# pwm-generator.net
KiCad netlist of a schematic drawn in EAGLE
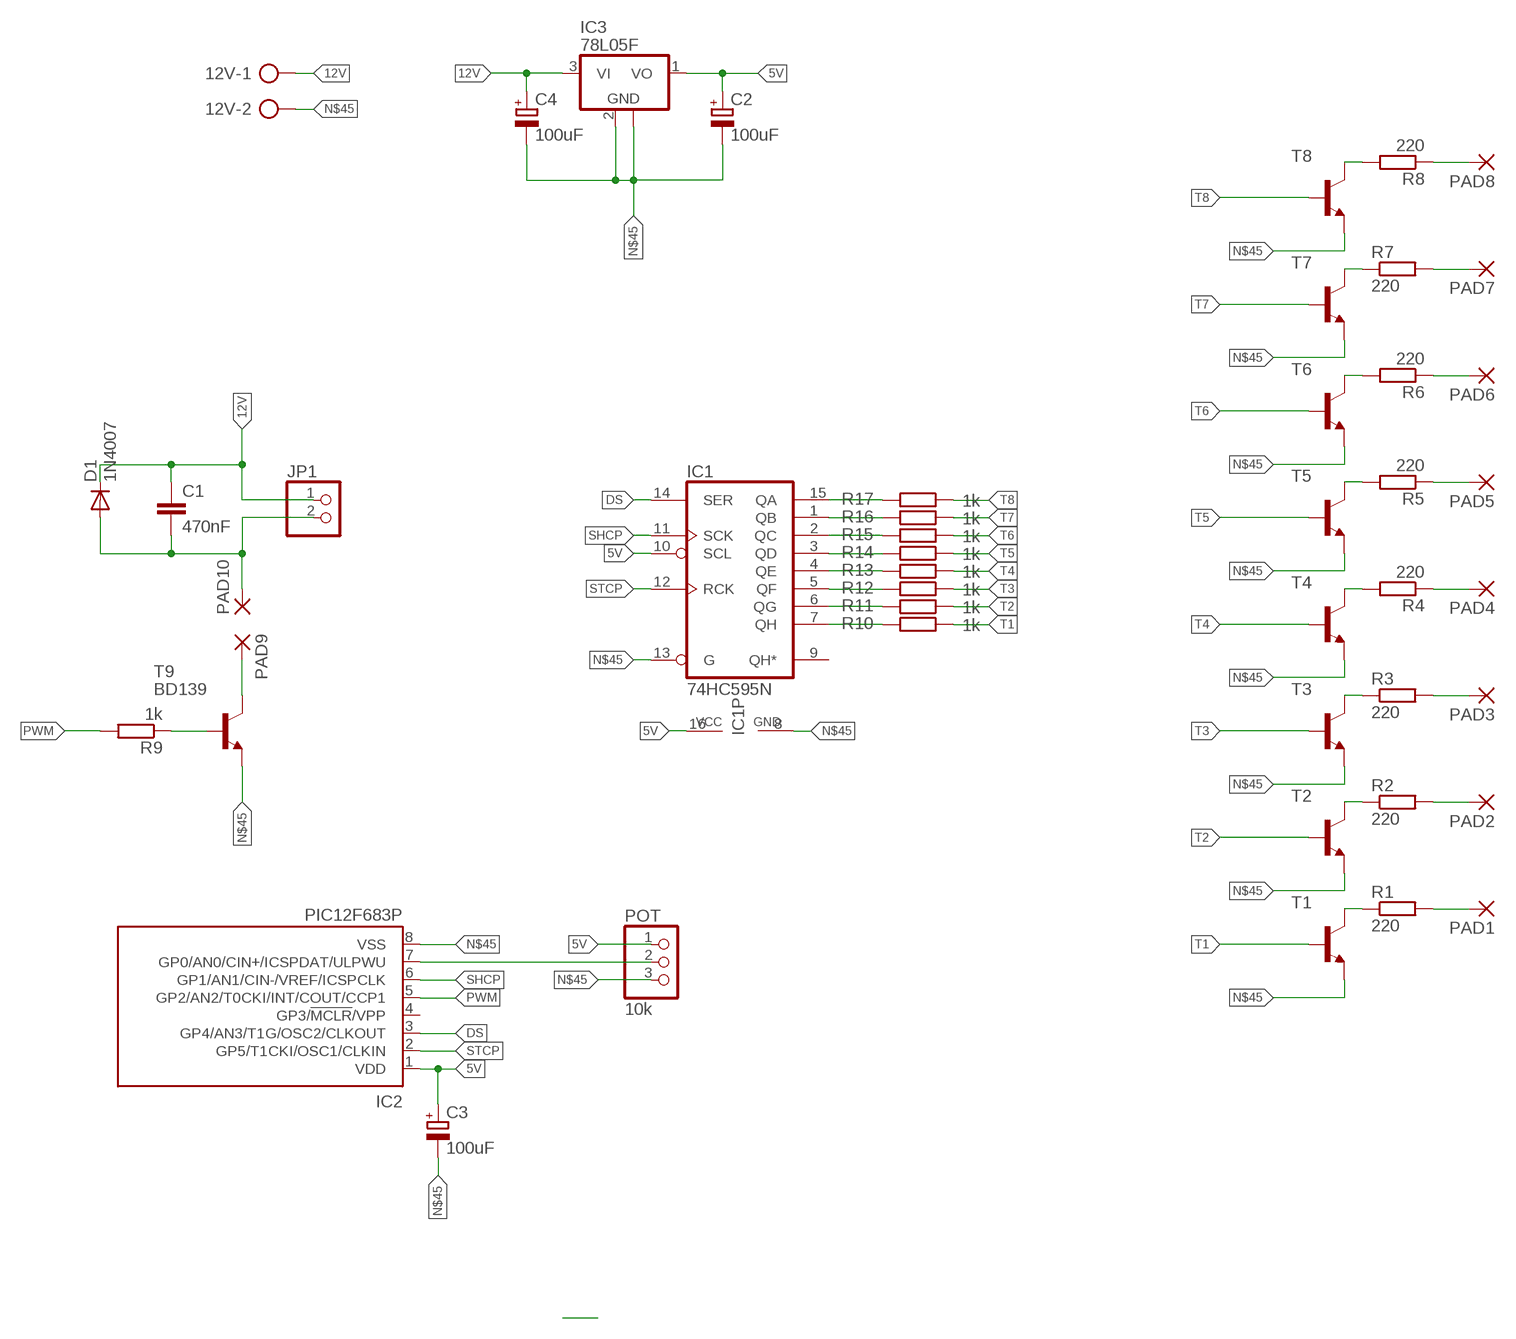
[diagram p0: schematic, sheet 1]

(export (version "E")
  (design (tool "Eeschema 10.0.6"))
  (components
    (comp (ref "12V")
      (value "AK500/2")
      (footprint "eagle-import:AK500_2")
      (libsource (lib "eagle-import") (part "AK500/2"))
    )
    (comp (ref "C1")
      (value "470nF")
      (footprint "eagle-import:C025-025X050")
      (libsource (lib "eagle-import") (part "C-EU025-025X050"))
    )
    (comp (ref "C2")
      (value "100uF")
      (footprint "eagle-import:E2-5")
      (libsource (lib "eagle-import") (part "CPOL-EUE2-5"))
    )
    (comp (ref "C3")
      (value "100uF")
      (footprint "eagle-import:E5-4")
      (libsource (lib "eagle-import") (part "CPOL-EUE5-4"))
    )
    (comp (ref "C4")
      (value "100uF")
      (footprint "eagle-import:E2-5")
      (libsource (lib "eagle-import") (part "CPOL-EUE2-5"))
    )
    (comp (ref "D1")
      (value "1N4007")
      (footprint "eagle-import:DO35-7")
      (libsource (lib "eagle-import") (part "1N4148DO35-7"))
    )
    (comp (ref "IC1")
      (value "74HC595N")
      (footprint "eagle-import:DIL16")
      (libsource (lib "eagle-import") (part "74595NHC"))
    )
    (comp (ref "IC2")
      (value "PIC12F683P")
      (footprint "eagle-import:DIL8")
      (fields (field (name "MF") "MICROCHIP") (field (name "MPN") "PIC12F683-I/P"))
      (libsource (lib "eagle-import") (part "PIC12F683P"))
    )
    (comp (ref "IC3")
      (value "78L05F")
      (footprint "eagle-import:SOT89")
      (libsource (lib "eagle-import") (part "78LF05"))
    )
    (comp (ref "JP1")
      (value "PINHD-1X2")
      (footprint "eagle-import:1X02")
      (libsource (lib "eagle-import") (part "PINHD-1X2"))
    )
    (comp (ref "PAD1")
      (value "SMD2")
      (footprint "eagle-import:SMD1,27-2,54")
      (libsource (lib "eagle-import") (part "SMD2"))
    )
    (comp (ref "PAD2")
      (value "SMD2")
      (footprint "eagle-import:SMD1,27-2,54")
      (libsource (lib "eagle-import") (part "SMD2"))
    )
    (comp (ref "PAD3")
      (value "SMD2")
      (footprint "eagle-import:SMD1,27-2,54")
      (libsource (lib "eagle-import") (part "SMD2"))
    )
    (comp (ref "PAD4")
      (value "SMD2")
      (footprint "eagle-import:SMD1,27-2,54")
      (libsource (lib "eagle-import") (part "SMD2"))
    )
    (comp (ref "PAD5")
      (value "SMD2")
      (footprint "eagle-import:SMD1,27-2,54")
      (libsource (lib "eagle-import") (part "SMD2"))
    )
    (comp (ref "PAD6")
      (value "SMD2")
      (footprint "eagle-import:SMD1,27-2,54")
      (libsource (lib "eagle-import") (part "SMD2"))
    )
    (comp (ref "PAD7")
      (value "SMD2")
      (footprint "eagle-import:SMD1,27-2,54")
      (libsource (lib "eagle-import") (part "SMD2"))
    )
    (comp (ref "PAD8")
      (value "SMD2")
      (footprint "eagle-import:SMD1,27-2,54")
      (libsource (lib "eagle-import") (part "SMD2"))
    )
    (comp (ref "PAD9")
      (value "1,6/0,8")
      (footprint "eagle-import:1,6_0,8")
      (libsource (lib "eagle-import") (part "1,6/0,8"))
    )
    (comp (ref "PAD10")
      (value "1,6/0,8")
      (footprint "eagle-import:1,6_0,8")
      (libsource (lib "eagle-import") (part "1,6/0,8"))
    )
    (comp (ref "POT")
      (value "10k")
      (footprint "eagle-import:1X03")
      (libsource (lib "eagle-import") (part "PINHD-1X3"))
    )
    (comp (ref "R1")
      (value "220")
      (footprint "eagle-import:M0805")
      (libsource (lib "eagle-import") (part "R-EU_M0805"))
    )
    (comp (ref "R2")
      (value "220")
      (footprint "eagle-import:M0805")
      (libsource (lib "eagle-import") (part "R-EU_M0805"))
    )
    (comp (ref "R3")
      (value "220")
      (footprint "eagle-import:M0805")
      (libsource (lib "eagle-import") (part "R-EU_M0805"))
    )
    (comp (ref "R4")
      (value "220")
      (footprint "eagle-import:M0805")
      (libsource (lib "eagle-import") (part "R-EU_M0805"))
    )
    (comp (ref "R5")
      (value "220")
      (footprint "eagle-import:M0805")
      (libsource (lib "eagle-import") (part "R-EU_M0805"))
    )
    (comp (ref "R6")
      (value "220")
      (footprint "eagle-import:M0805")
      (libsource (lib "eagle-import") (part "R-EU_M0805"))
    )
    (comp (ref "R7")
      (value "220")
      (footprint "eagle-import:M0805")
      (libsource (lib "eagle-import") (part "R-EU_M0805"))
    )
    (comp (ref "R8")
      (value "220")
      (footprint "eagle-import:M0805")
      (libsource (lib "eagle-import") (part "R-EU_M0805"))
    )
    (comp (ref "R9")
      (value "1k")
      (footprint "eagle-import:M0805")
      (libsource (lib "eagle-import") (part "R-EU_M0805"))
    )
    (comp (ref "R10")
      (value "1k")
      (footprint "eagle-import:M0805")
      (libsource (lib "eagle-import") (part "R-EU_M0805"))
    )
    (comp (ref "R11")
      (value "1k")
      (footprint "eagle-import:M0805")
      (libsource (lib "eagle-import") (part "R-EU_M0805"))
    )
    (comp (ref "R12")
      (value "1k")
      (footprint "eagle-import:M0805")
      (libsource (lib "eagle-import") (part "R-EU_M0805"))
    )
    (comp (ref "R13")
      (value "1k")
      (footprint "eagle-import:M0805")
      (libsource (lib "eagle-import") (part "R-EU_M0805"))
    )
    (comp (ref "R14")
      (value "1k")
      (footprint "eagle-import:M0805")
      (libsource (lib "eagle-import") (part "R-EU_M0805"))
    )
    (comp (ref "R15")
      (value "1k")
      (footprint "eagle-import:M0805")
      (libsource (lib "eagle-import") (part "R-EU_M0805"))
    )
    (comp (ref "R16")
      (value "1k")
      (footprint "eagle-import:M0805")
      (libsource (lib "eagle-import") (part "R-EU_M0805"))
    )
    (comp (ref "R17")
      (value "1k")
      (footprint "eagle-import:M0805")
      (libsource (lib "eagle-import") (part "R-EU_M0805"))
    )
    (comp (ref "T1")
      (value "-NPN-SOT23-EBC")
      (footprint "eagle-import:SOT23-EBC")
      (libsource (lib "eagle-import") (part "-NPN-SOT23-EBC"))
    )
    (comp (ref "T2")
      (value "-NPN-SOT23-EBC")
      (footprint "eagle-import:SOT23-EBC")
      (libsource (lib "eagle-import") (part "-NPN-SOT23-EBC"))
    )
    (comp (ref "T3")
      (value "-NPN-SOT23-EBC")
      (footprint "eagle-import:SOT23-EBC")
      (libsource (lib "eagle-import") (part "-NPN-SOT23-EBC"))
    )
    (comp (ref "T4")
      (value "-NPN-SOT23-EBC")
      (footprint "eagle-import:SOT23-EBC")
      (libsource (lib "eagle-import") (part "-NPN-SOT23-EBC"))
    )
    (comp (ref "T5")
      (value "-NPN-SOT23-EBC")
      (footprint "eagle-import:SOT23-EBC")
      (libsource (lib "eagle-import") (part "-NPN-SOT23-EBC"))
    )
    (comp (ref "T6")
      (value "-NPN-SOT23-EBC")
      (footprint "eagle-import:SOT23-EBC")
      (libsource (lib "eagle-import") (part "-NPN-SOT23-EBC"))
    )
    (comp (ref "T7")
      (value "-NPN-SOT23-EBC")
      (footprint "eagle-import:SOT23-EBC")
      (libsource (lib "eagle-import") (part "-NPN-SOT23-EBC"))
    )
    (comp (ref "T8")
      (value "-NPN-SOT23-EBC")
      (footprint "eagle-import:SOT23-EBC")
      (libsource (lib "eagle-import") (part "-NPN-SOT23-EBC"))
    )
    (comp (ref "T9")
      (value "BD139")
      (footprint "eagle-import:TO126")
      (libsource (lib "eagle-import") (part "BD139"))
    )
  )
  (nets
    (net (code "1") (name "5V") (class "Default")
      (node (ref "C2") (pin "+") (pinfunction "+_+") (pintype "passive"))
      (node (ref "C3") (pin "+") (pinfunction "+_+") (pintype "passive"))
      (node (ref "IC1") (pin "10") (pinfunction "SCL_10") (pintype "input"))
      (node (ref "IC1") (pin "16") (pinfunction "VCC_16") (pintype "power_in"))
      (node (ref "IC2") (pin "1") (pinfunction "VDD_1") (pintype "power_in"))
      (node (ref "IC3") (pin "1") (pinfunction "VO_1") (pintype "passive"))
      (node (ref "POT") (pin "1") (pinfunction "1_1") (pintype "passive"))
    )
    (net (code "2") (name "12V") (class "Default")
      (node (ref "12V") (pin "1") (pinfunction "KL_1") (pintype "passive"))
      (node (ref "C1") (pin "1") (pinfunction "1_1") (pintype "passive"))
      (node (ref "C4") (pin "+") (pinfunction "+_+") (pintype "passive"))
      (node (ref "D1") (pin "C") (pinfunction "C_C") (pintype "passive"))
      (node (ref "IC3") (pin "3") (pinfunction "VI_3") (pintype "input"))
      (node (ref "JP1") (pin "1") (pinfunction "1_1") (pintype "passive"))
    )
    (net (code "3") (name "DS") (class "Default")
      (node (ref "IC1") (pin "14") (pinfunction "SER_14") (pintype "input"))
      (node (ref "IC2") (pin "3") (pinfunction "GP4/AN3/T1G/OSC2/CLKOUT_3") (pintype "bidirectional"))
    )
    (net (code "4") (name "N$45") (class "Default")
      (node (ref "12V") (pin "2") (pinfunction "KL_2") (pintype "passive"))
      (node (ref "C2") (pin "-") (pinfunction "-_-") (pintype "passive"))
      (node (ref "C3") (pin "-") (pinfunction "-_-") (pintype "passive"))
      (node (ref "C4") (pin "-") (pinfunction "-_-") (pintype "passive"))
      (node (ref "IC1") (pin "13") (pinfunction "G_13") (pintype "input"))
      (node (ref "IC1") (pin "8") (pinfunction "GND_8") (pintype "power_in"))
      (node (ref "IC2") (pin "8") (pinfunction "VSS_8") (pintype "power_in"))
      (node (ref "IC3") (pin "2") (pinfunction "GND_2") (pintype "passive"))
      (node (ref "IC3") (pin "2@1") (pinfunction "GND_2@1") (pintype "passive"))
      (node (ref "POT") (pin "3") (pinfunction "3_3") (pintype "passive"))
      (node (ref "T1") (pin "E") (pinfunction "E_E") (pintype "passive"))
      (node (ref "T2") (pin "E") (pinfunction "E_E") (pintype "passive"))
      (node (ref "T3") (pin "E") (pinfunction "E_E") (pintype "passive"))
      (node (ref "T4") (pin "E") (pinfunction "E_E") (pintype "passive"))
      (node (ref "T5") (pin "E") (pinfunction "E_E") (pintype "passive"))
      (node (ref "T6") (pin "E") (pinfunction "E_E") (pintype "passive"))
      (node (ref "T7") (pin "E") (pinfunction "E_E") (pintype "passive"))
      (node (ref "T8") (pin "E") (pinfunction "E_E") (pintype "passive"))
      (node (ref "T9") (pin "1") (pinfunction "E_1") (pintype "passive"))
    )
    (net (code "5") (name "Net-(IC1A-QA)") (class "Default")
      (node (ref "IC1") (pin "15") (pinfunction "QA_15") (pintype "tri_state"))
      (node (ref "R17") (pin "2") (pinfunction "2_2") (pintype "passive"))
    )
    (net (code "6") (name "Net-(IC1A-QB)") (class "Default")
      (node (ref "IC1") (pin "1") (pinfunction "QB_1") (pintype "tri_state"))
      (node (ref "R16") (pin "2") (pinfunction "2_2") (pintype "passive"))
    )
    (net (code "7") (name "Net-(IC1A-QC)") (class "Default")
      (node (ref "IC1") (pin "2") (pinfunction "QC_2") (pintype "tri_state"))
      (node (ref "R15") (pin "2") (pinfunction "2_2") (pintype "passive"))
    )
    (net (code "8") (name "Net-(IC1A-QD)") (class "Default")
      (node (ref "IC1") (pin "3") (pinfunction "QD_3") (pintype "tri_state"))
      (node (ref "R14") (pin "2") (pinfunction "2_2") (pintype "passive"))
    )
    (net (code "9") (name "Net-(IC1A-QE)") (class "Default")
      (node (ref "IC1") (pin "4") (pinfunction "QE_4") (pintype "tri_state"))
      (node (ref "R13") (pin "2") (pinfunction "2_2") (pintype "passive"))
    )
    (net (code "10") (name "Net-(IC1A-QF)") (class "Default")
      (node (ref "IC1") (pin "5") (pinfunction "QF_5") (pintype "tri_state"))
      (node (ref "R12") (pin "2") (pinfunction "2_2") (pintype "passive"))
    )
    (net (code "11") (name "Net-(IC1A-QG)") (class "Default")
      (node (ref "IC1") (pin "6") (pinfunction "QG_6") (pintype "tri_state"))
      (node (ref "R11") (pin "2") (pinfunction "2_2") (pintype "passive"))
    )
    (net (code "12") (name "Net-(IC1A-QH)") (class "Default")
      (node (ref "IC1") (pin "7") (pinfunction "QH_7") (pintype "tri_state"))
      (node (ref "R10") (pin "2") (pinfunction "2_2") (pintype "passive"))
    )
    (net (code "13") (name "Net-(IC2-GP0{slash}AN0{slash}CIN+{slash}ICSPDAT{slash}ULPWU)") (class "Default")
      (node (ref "IC2") (pin "7") (pinfunction "GP0/AN0/CIN+/ICSPDAT/ULPWU_7") (pintype "bidirectional"))
      (node (ref "POT") (pin "2") (pinfunction "2_2") (pintype "passive"))
    )
    (net (code "14") (name "Net-(PAD1-P)") (class "Default")
      (node (ref "PAD1") (pin "1") (pinfunction "P_1") (pintype "passive"))
      (node (ref "R1") (pin "2") (pinfunction "2_2") (pintype "passive"))
    )
    (net (code "15") (name "Net-(PAD2-P)") (class "Default")
      (node (ref "PAD2") (pin "1") (pinfunction "P_1") (pintype "passive"))
      (node (ref "R2") (pin "2") (pinfunction "2_2") (pintype "passive"))
    )
    (net (code "16") (name "Net-(PAD3-P)") (class "Default")
      (node (ref "PAD3") (pin "1") (pinfunction "P_1") (pintype "passive"))
      (node (ref "R3") (pin "2") (pinfunction "2_2") (pintype "passive"))
    )
    (net (code "17") (name "Net-(PAD4-P)") (class "Default")
      (node (ref "PAD4") (pin "1") (pinfunction "P_1") (pintype "passive"))
      (node (ref "R4") (pin "1") (pinfunction "1_1") (pintype "passive"))
    )
    (net (code "18") (name "Net-(PAD5-P)") (class "Default")
      (node (ref "PAD5") (pin "1") (pinfunction "P_1") (pintype "passive"))
      (node (ref "R5") (pin "1") (pinfunction "1_1") (pintype "passive"))
    )
    (net (code "19") (name "Net-(PAD6-P)") (class "Default")
      (node (ref "PAD6") (pin "1") (pinfunction "P_1") (pintype "passive"))
      (node (ref "R6") (pin "1") (pinfunction "1_1") (pintype "passive"))
    )
    (net (code "20") (name "Net-(PAD7-P)") (class "Default")
      (node (ref "PAD7") (pin "1") (pinfunction "P_1") (pintype "passive"))
      (node (ref "R7") (pin "2") (pinfunction "2_2") (pintype "passive"))
    )
    (net (code "21") (name "Net-(PAD8-P)") (class "Default")
      (node (ref "PAD8") (pin "1") (pinfunction "P_1") (pintype "passive"))
      (node (ref "R8") (pin "1") (pinfunction "1_1") (pintype "passive"))
    )
    (net (code "22") (name "Net-(PAD9-P)") (class "Default")
      (node (ref "PAD9") (pin "1") (pinfunction "P_1") (pintype "passive"))
      (node (ref "T9") (pin "2") (pinfunction "C_2") (pintype "passive"))
    )
    (net (code "23") (name "Net-(PAD10-P)") (class "Default")
      (node (ref "C1") (pin "2") (pinfunction "2_2") (pintype "passive"))
      (node (ref "D1") (pin "A") (pinfunction "A_A") (pintype "passive"))
      (node (ref "JP1") (pin "2") (pinfunction "2_2") (pintype "passive"))
      (node (ref "PAD10") (pin "1") (pinfunction "P_1") (pintype "passive"))
    )
    (net (code "24") (name "Net-(R1-Pad1)") (class "Default")
      (node (ref "R1") (pin "1") (pinfunction "1_1") (pintype "passive"))
      (node (ref "T1") (pin "C") (pinfunction "C_C") (pintype "passive"))
    )
    (net (code "25") (name "Net-(R2-Pad1)") (class "Default")
      (node (ref "R2") (pin "1") (pinfunction "1_1") (pintype "passive"))
      (node (ref "T2") (pin "C") (pinfunction "C_C") (pintype "passive"))
    )
    (net (code "26") (name "Net-(R3-Pad1)") (class "Default")
      (node (ref "R3") (pin "1") (pinfunction "1_1") (pintype "passive"))
      (node (ref "T3") (pin "C") (pinfunction "C_C") (pintype "passive"))
    )
    (net (code "27") (name "Net-(R4-Pad2)") (class "Default")
      (node (ref "R4") (pin "2") (pinfunction "2_2") (pintype "passive"))
      (node (ref "T4") (pin "C") (pinfunction "C_C") (pintype "passive"))
    )
    (net (code "28") (name "Net-(R5-Pad2)") (class "Default")
      (node (ref "R5") (pin "2") (pinfunction "2_2") (pintype "passive"))
      (node (ref "T5") (pin "C") (pinfunction "C_C") (pintype "passive"))
    )
    (net (code "29") (name "Net-(R6-Pad2)") (class "Default")
      (node (ref "R6") (pin "2") (pinfunction "2_2") (pintype "passive"))
      (node (ref "T6") (pin "C") (pinfunction "C_C") (pintype "passive"))
    )
    (net (code "30") (name "Net-(R7-Pad1)") (class "Default")
      (node (ref "R7") (pin "1") (pinfunction "1_1") (pintype "passive"))
      (node (ref "T7") (pin "C") (pinfunction "C_C") (pintype "passive"))
    )
    (net (code "31") (name "Net-(R8-Pad2)") (class "Default")
      (node (ref "R8") (pin "2") (pinfunction "2_2") (pintype "passive"))
      (node (ref "T8") (pin "C") (pinfunction "C_C") (pintype "passive"))
    )
    (net (code "32") (name "Net-(T9-B)") (class "Default")
      (node (ref "R9") (pin "1") (pinfunction "1_1") (pintype "passive"))
      (node (ref "T9") (pin "3") (pinfunction "B_3") (pintype "passive"))
    )
    (net (code "33") (name "PWM") (class "Default")
      (node (ref "IC2") (pin "5") (pinfunction "GP2/AN2/T0CKI/INT/COUT/CCP1_5") (pintype "bidirectional"))
      (node (ref "R9") (pin "2") (pinfunction "2_2") (pintype "passive"))
    )
    (net (code "34") (name "SHCP") (class "Default")
      (node (ref "IC1") (pin "11") (pinfunction "SCK_11") (pintype "input"))
      (node (ref "IC2") (pin "6") (pinfunction "GP1/AN1/CIN-/VREF/ICSPCLK_6") (pintype "bidirectional"))
    )
    (net (code "35") (name "STCP") (class "Default")
      (node (ref "IC1") (pin "12") (pinfunction "RCK_12") (pintype "input"))
      (node (ref "IC2") (pin "2") (pinfunction "GP5/T1CKI/OSC1/CLKIN_2") (pintype "bidirectional"))
    )
    (net (code "36") (name "T1") (class "Default")
      (node (ref "R10") (pin "1") (pinfunction "1_1") (pintype "passive"))
      (node (ref "T1") (pin "B") (pinfunction "B_B") (pintype "passive"))
    )
    (net (code "37") (name "T2") (class "Default")
      (node (ref "R11") (pin "1") (pinfunction "1_1") (pintype "passive"))
      (node (ref "T2") (pin "B") (pinfunction "B_B") (pintype "passive"))
    )
    (net (code "38") (name "T3") (class "Default")
      (node (ref "R12") (pin "1") (pinfunction "1_1") (pintype "passive"))
      (node (ref "T3") (pin "B") (pinfunction "B_B") (pintype "passive"))
    )
    (net (code "39") (name "T4") (class "Default")
      (node (ref "R13") (pin "1") (pinfunction "1_1") (pintype "passive"))
      (node (ref "T4") (pin "B") (pinfunction "B_B") (pintype "passive"))
    )
    (net (code "40") (name "T5") (class "Default")
      (node (ref "R14") (pin "1") (pinfunction "1_1") (pintype "passive"))
      (node (ref "T5") (pin "B") (pinfunction "B_B") (pintype "passive"))
    )
    (net (code "41") (name "T6") (class "Default")
      (node (ref "R15") (pin "1") (pinfunction "1_1") (pintype "passive"))
      (node (ref "T6") (pin "B") (pinfunction "B_B") (pintype "passive"))
    )
    (net (code "42") (name "T7") (class "Default")
      (node (ref "R16") (pin "1") (pinfunction "1_1") (pintype "passive"))
      (node (ref "T7") (pin "B") (pinfunction "B_B") (pintype "passive"))
    )
    (net (code "43") (name "T8") (class "Default")
      (node (ref "R17") (pin "1") (pinfunction "1_1") (pintype "passive"))
      (node (ref "T8") (pin "B") (pinfunction "B_B") (pintype "passive"))
    )
    (net (code "44") (name "unconnected-(IC1A-QH*-Pad9)") (class "Default")
      (node (ref "IC1") (pin "9") (pinfunction "QH*_9") (pintype "tri_state"))
    )
    (net (code "45") (name "unconnected-(IC2-GP3{slash}~{MCLR}{slash}VPP-Pad4)") (class "Default")
      (node (ref "IC2") (pin "4") (pinfunction "GP3/~{MCLR}/VPP_4") (pintype "bidirectional"))
    )
  )
)
